# LowVBoard_01.net
KiCad netlist of a schematic drawn in EAGLE
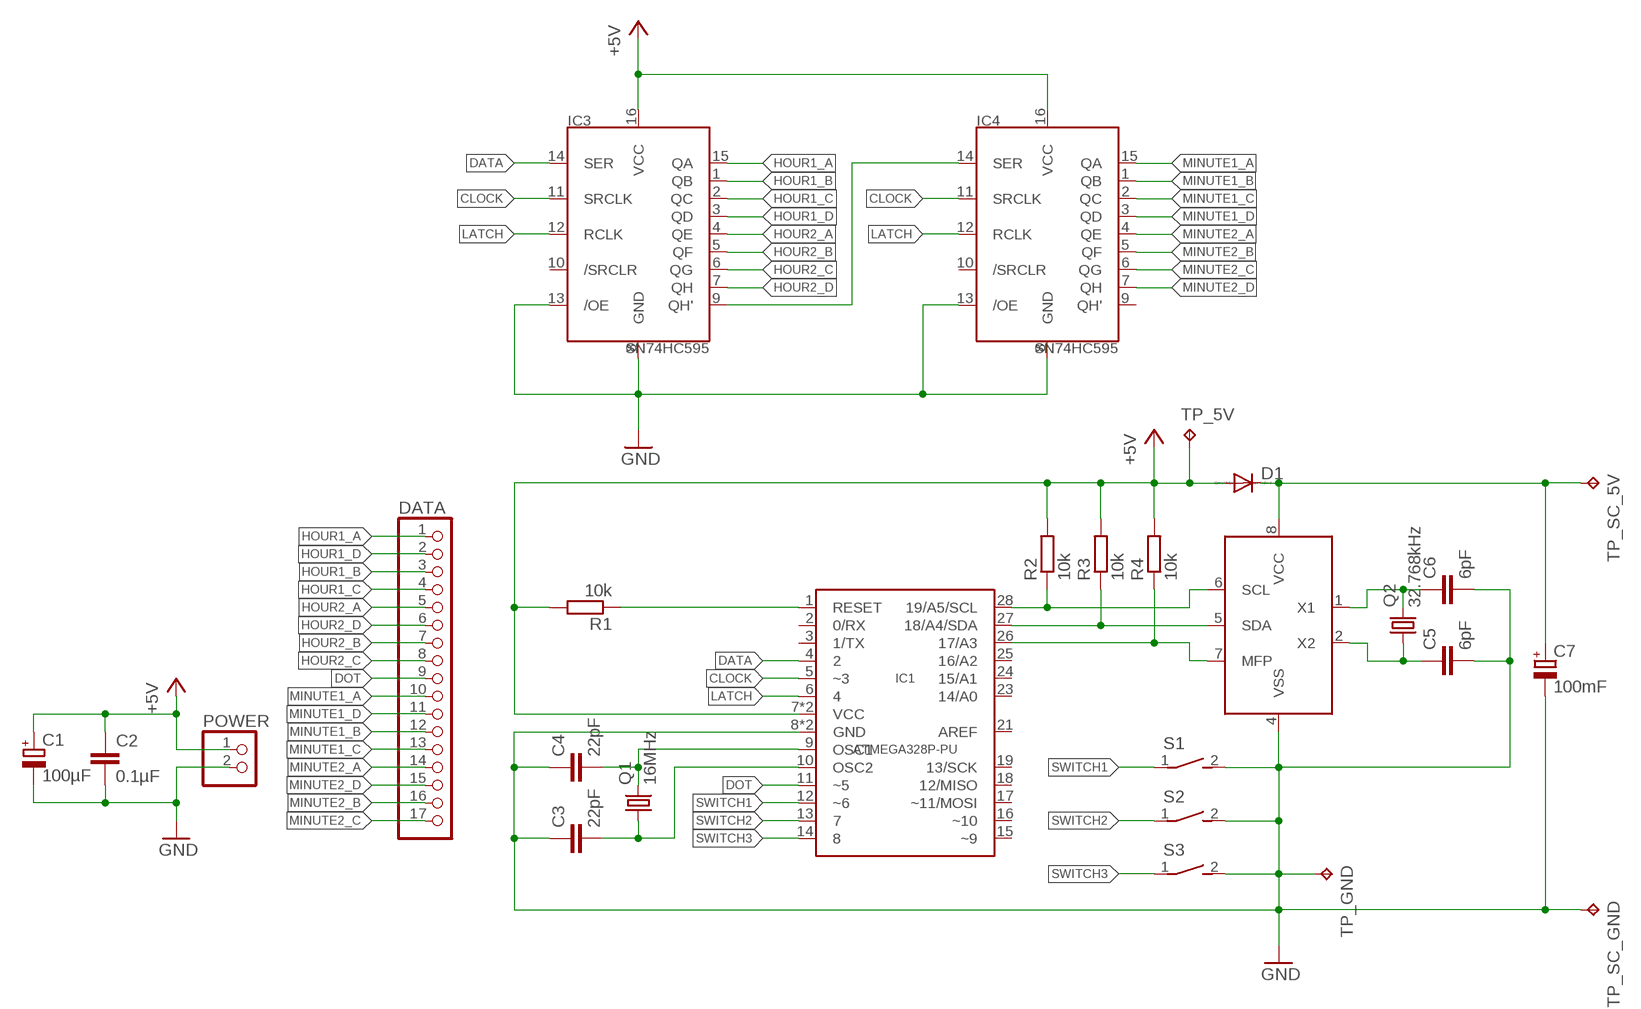
[diagram p0: schematic, sheet 1]

(export (version "E")
  (design (tool "Eeschema 10.0.6"))
  (components
    (comp (ref "C1")
      (value "100µF")
      (footprint "eagle-import:E2-5")
      (libsource (lib "eagle-import") (part "CPOL-EUE2-5"))
    )
    (comp (ref "C2")
      (value "0.1µF")
      (footprint "eagle-import:C025-024X044")
      (libsource (lib "eagle-import") (part "C-EU025-024X044"))
    )
    (comp (ref "C3")
      (value "22pF")
      (footprint "eagle-import:C025-024X044")
      (libsource (lib "eagle-import") (part "C-EU025-024X044"))
    )
    (comp (ref "C4")
      (value "22pF")
      (footprint "eagle-import:C025-024X044")
      (libsource (lib "eagle-import") (part "C-EU025-024X044"))
    )
    (comp (ref "C5")
      (value "6pF")
      (footprint "eagle-import:C025-024X044")
      (libsource (lib "eagle-import") (part "C-EU025-024X044"))
    )
    (comp (ref "C6")
      (value "6pF")
      (footprint "eagle-import:C025-024X044")
      (libsource (lib "eagle-import") (part "C-EU025-024X044"))
    )
    (comp (ref "C7")
      (value "100mF")
      (footprint "eagle-import:SUPERCAP-11.5")
      (libsource (lib "eagle-import") (part "FTW0H104ZF"))
    )
    (comp (ref "D1")
      (value "DIODE-DO201-15")
      (footprint "eagle-import:DO201-15")
      (libsource (lib "eagle-import") (part "DIODE-DO201-15"))
    )
    (comp (ref "DATA")
      (value "PINHD-1X17")
      (footprint "eagle-import:1X17")
      (libsource (lib "eagle-import") (part "PINHD-1X17"))
    )
    (comp (ref "IC1")
      (value "ATMEGA328P-PU")
      (footprint "eagle-import:DIP28")
      (libsource (lib "eagle-import") (part "ATMEGA328P-PU"))
    )
    (comp (ref "IC2")
      (value "MCP7940M")
      (footprint "eagle-import:DIL8")
      (libsource (lib "eagle-import") (part "MCP7940M-I/P"))
    )
    (comp (ref "IC3")
      (value "SN74HC595")
      (footprint "eagle-import:DIL16")
      (libsource (lib "eagle-import") (part "SN74HC595"))
    )
    (comp (ref "IC4")
      (value "SN74HC595")
      (footprint "eagle-import:DIL16")
      (libsource (lib "eagle-import") (part "SN74HC595"))
    )
    (comp (ref "POWER")
      (value "PINHD-1X2")
      (footprint "eagle-import:1X02")
      (libsource (lib "eagle-import") (part "PINHD-1X2"))
    )
    (comp (ref "Q1")
      (value "16MHz")
      (footprint "eagle-import:HC49_S")
      (libsource (lib "eagle-import") (part "CRYSTALHC49S"))
    )
    (comp (ref "Q2")
      (value "32.768kHz")
      (footprint "eagle-import:CFS-206")
      (libsource (lib "eagle-import") (part "CFS-206"))
    )
    (comp (ref "R1")
      (value "10k")
      (footprint "eagle-import:0207_7")
      (libsource (lib "eagle-import") (part "R-EU_0207/7"))
    )
    (comp (ref "R2")
      (value "10k")
      (footprint "eagle-import:0207_7")
      (libsource (lib "eagle-import") (part "R-EU_0207/7"))
    )
    (comp (ref "R3")
      (value "10k")
      (footprint "eagle-import:0207_7")
      (libsource (lib "eagle-import") (part "R-EU_0207/7"))
    )
    (comp (ref "R4")
      (value "10k")
      (footprint "eagle-import:0207_7")
      (libsource (lib "eagle-import") (part "R-EU_0207/7"))
    )
    (comp (ref "S1")
      (value "GPTS203211B")
      (footprint "eagle-import:GPTS203211B")
      (libsource (lib "eagle-import") (part "GPTS203211B"))
    )
    (comp (ref "S2")
      (value "GPTS203211B")
      (footprint "eagle-import:GPTS203211B")
      (libsource (lib "eagle-import") (part "GPTS203211B"))
    )
    (comp (ref "S3")
      (value "GPTS203211B")
      (footprint "eagle-import:GPTS203211B")
      (libsource (lib "eagle-import") (part "GPTS203211B"))
    )
    (comp (ref "TP_5V")
      (value "TPPAD1-13")
      (footprint "eagle-import:P1-13")
      (libsource (lib "eagle-import") (part "TPPAD1-13"))
    )
    (comp (ref "TP_GND")
      (value "TPPAD1-13")
      (footprint "eagle-import:P1-13")
      (libsource (lib "eagle-import") (part "TPPAD1-13"))
    )
    (comp (ref "TP_SC_5V")
      (value "TPPAD1-13")
      (footprint "eagle-import:P1-13")
      (libsource (lib "eagle-import") (part "TPPAD1-13"))
    )
    (comp (ref "TP_SC_GND")
      (value "TPPAD1-13")
      (footprint "eagle-import:P1-13")
      (libsource (lib "eagle-import") (part "TPPAD1-13"))
    )
  )
  (nets
    (net (code "1") (name "+5V") (class "Default")
      (node (ref "C1") (pin "+") (pinfunction "+_+") (pintype "passive"))
      (node (ref "C2") (pin "1") (pinfunction "1_1") (pintype "passive"))
      (node (ref "D1") (pin "A") (pinfunction "A_A") (pintype "passive"))
      (node (ref "IC1") (pin "20") (pinfunction "VCC_20") (pintype "bidirectional"))
      (node (ref "IC1") (pin "7") (pinfunction "VCC_7") (pintype "bidirectional"))
      (node (ref "IC3") (pin "16") (pinfunction "VCC_16") (pintype "bidirectional"))
      (node (ref "IC4") (pin "16") (pinfunction "VCC_16") (pintype "bidirectional"))
      (node (ref "POWER") (pin "1") (pinfunction "1_1") (pintype "passive"))
      (node (ref "R1") (pin "2") (pinfunction "2_2") (pintype "passive"))
      (node (ref "R2") (pin "2") (pinfunction "2_2") (pintype "passive"))
      (node (ref "R3") (pin "2") (pinfunction "2_2") (pintype "passive"))
      (node (ref "R4") (pin "2") (pinfunction "2_2") (pintype "passive"))
      (node (ref "TP_5V") (pin "TP") (pinfunction "TP_TP") (pintype "input"))
    )
    (net (code "2") (name "CLOCK") (class "Default")
      (node (ref "IC1") (pin "5") (pinfunction "~{3}_5") (pintype "bidirectional"))
      (node (ref "IC3") (pin "11") (pinfunction "SRCLK_11") (pintype "bidirectional"))
      (node (ref "IC4") (pin "11") (pinfunction "SRCLK_11") (pintype "bidirectional"))
    )
    (net (code "3") (name "DATA") (class "Default")
      (node (ref "IC1") (pin "4") (pinfunction "2_4") (pintype "bidirectional"))
      (node (ref "IC3") (pin "14") (pinfunction "SER_14") (pintype "bidirectional"))
    )
    (net (code "4") (name "DOT") (class "Default")
      (node (ref "DATA") (pin "9") (pinfunction "9_9") (pintype "passive"))
      (node (ref "IC1") (pin "11") (pinfunction "~{5}_11") (pintype "bidirectional"))
    )
    (net (code "5") (name "GND") (class "Default")
      (node (ref "C1") (pin "-") (pinfunction "-_-") (pintype "passive"))
      (node (ref "C2") (pin "2") (pinfunction "2_2") (pintype "passive"))
      (node (ref "C3") (pin "1") (pinfunction "1_1") (pintype "passive"))
      (node (ref "C4") (pin "1") (pinfunction "1_1") (pintype "passive"))
      (node (ref "C5") (pin "2") (pinfunction "2_2") (pintype "passive"))
      (node (ref "C6") (pin "2") (pinfunction "2_2") (pintype "passive"))
      (node (ref "C7") (pin "-") (pinfunction "-_-") (pintype "passive"))
      (node (ref "IC1") (pin "22") (pinfunction "GND_22") (pintype "bidirectional"))
      (node (ref "IC1") (pin "8") (pinfunction "GND_8") (pintype "bidirectional"))
      (node (ref "IC2") (pin "4") (pinfunction "VSS_4") (pintype "bidirectional"))
      (node (ref "IC3") (pin "13") (pinfunction "/OE_13") (pintype "bidirectional"))
      (node (ref "IC3") (pin "8") (pinfunction "GND_8") (pintype "bidirectional"))
      (node (ref "IC4") (pin "13") (pinfunction "/OE_13") (pintype "bidirectional"))
      (node (ref "IC4") (pin "8") (pinfunction "GND_8") (pintype "bidirectional"))
      (node (ref "POWER") (pin "2") (pinfunction "2_2") (pintype "passive"))
      (node (ref "S1") (pin "2") (pinfunction "S_2") (pintype "passive"))
      (node (ref "S2") (pin "2") (pinfunction "S_2") (pintype "passive"))
      (node (ref "S3") (pin "2") (pinfunction "S_2") (pintype "passive"))
      (node (ref "TP_GND") (pin "TP") (pinfunction "TP_TP") (pintype "input"))
      (node (ref "TP_SC_GND") (pin "TP") (pinfunction "TP_TP") (pintype "input"))
    )
    (net (code "6") (name "HOUR1_A") (class "Default")
      (node (ref "DATA") (pin "1") (pinfunction "1_1") (pintype "passive"))
      (node (ref "IC3") (pin "15") (pinfunction "QA_15") (pintype "bidirectional"))
    )
    (net (code "7") (name "HOUR1_B") (class "Default")
      (node (ref "DATA") (pin "3") (pinfunction "3_3") (pintype "passive"))
      (node (ref "IC3") (pin "1") (pinfunction "QB_1") (pintype "bidirectional"))
    )
    (net (code "8") (name "HOUR1_C") (class "Default")
      (node (ref "DATA") (pin "4") (pinfunction "4_4") (pintype "passive"))
      (node (ref "IC3") (pin "2") (pinfunction "QC_2") (pintype "bidirectional"))
    )
    (net (code "9") (name "HOUR1_D") (class "Default")
      (node (ref "DATA") (pin "2") (pinfunction "2_2") (pintype "passive"))
      (node (ref "IC3") (pin "3") (pinfunction "QD_3") (pintype "bidirectional"))
    )
    (net (code "10") (name "HOUR2_A") (class "Default")
      (node (ref "DATA") (pin "5") (pinfunction "5_5") (pintype "passive"))
      (node (ref "IC3") (pin "4") (pinfunction "QE_4") (pintype "bidirectional"))
    )
    (net (code "11") (name "HOUR2_B") (class "Default")
      (node (ref "DATA") (pin "7") (pinfunction "7_7") (pintype "passive"))
      (node (ref "IC3") (pin "5") (pinfunction "QF_5") (pintype "bidirectional"))
    )
    (net (code "12") (name "HOUR2_C") (class "Default")
      (node (ref "DATA") (pin "8") (pinfunction "8_8") (pintype "passive"))
      (node (ref "IC3") (pin "6") (pinfunction "QG_6") (pintype "bidirectional"))
    )
    (net (code "13") (name "HOUR2_D") (class "Default")
      (node (ref "DATA") (pin "6") (pinfunction "6_6") (pintype "passive"))
      (node (ref "IC3") (pin "7") (pinfunction "QH_7") (pintype "bidirectional"))
    )
    (net (code "14") (name "LATCH") (class "Default")
      (node (ref "IC1") (pin "6") (pinfunction "4_6") (pintype "bidirectional"))
      (node (ref "IC3") (pin "12") (pinfunction "RCLK_12") (pintype "bidirectional"))
      (node (ref "IC4") (pin "12") (pinfunction "RCLK_12") (pintype "bidirectional"))
    )
    (net (code "15") (name "MINUTE1_A") (class "Default")
      (node (ref "DATA") (pin "10") (pinfunction "10_10") (pintype "passive"))
      (node (ref "IC4") (pin "15") (pinfunction "QA_15") (pintype "bidirectional"))
    )
    (net (code "16") (name "MINUTE1_B") (class "Default")
      (node (ref "DATA") (pin "12") (pinfunction "12_12") (pintype "passive"))
      (node (ref "IC4") (pin "1") (pinfunction "QB_1") (pintype "bidirectional"))
    )
    (net (code "17") (name "MINUTE1_C") (class "Default")
      (node (ref "DATA") (pin "13") (pinfunction "13_13") (pintype "passive"))
      (node (ref "IC4") (pin "2") (pinfunction "QC_2") (pintype "bidirectional"))
    )
    (net (code "18") (name "MINUTE1_D") (class "Default")
      (node (ref "DATA") (pin "11") (pinfunction "11_11") (pintype "passive"))
      (node (ref "IC4") (pin "3") (pinfunction "QD_3") (pintype "bidirectional"))
    )
    (net (code "19") (name "MINUTE2_A") (class "Default")
      (node (ref "DATA") (pin "14") (pinfunction "14_14") (pintype "passive"))
      (node (ref "IC4") (pin "4") (pinfunction "QE_4") (pintype "bidirectional"))
    )
    (net (code "20") (name "MINUTE2_B") (class "Default")
      (node (ref "DATA") (pin "16") (pinfunction "16_16") (pintype "passive"))
      (node (ref "IC4") (pin "5") (pinfunction "QF_5") (pintype "bidirectional"))
    )
    (net (code "21") (name "MINUTE2_C") (class "Default")
      (node (ref "DATA") (pin "17") (pinfunction "17_17") (pintype "passive"))
      (node (ref "IC4") (pin "6") (pinfunction "QG_6") (pintype "bidirectional"))
    )
    (net (code "22") (name "MINUTE2_D") (class "Default")
      (node (ref "DATA") (pin "15") (pinfunction "15_15") (pintype "passive"))
      (node (ref "IC4") (pin "7") (pinfunction "QH_7") (pintype "bidirectional"))
    )
    (net (code "23") (name "Net-(IC1-17{slash}A3)") (class "Default")
      (node (ref "IC1") (pin "26") (pinfunction "17/A3_26") (pintype "bidirectional"))
      (node (ref "IC2") (pin "7") (pinfunction "MFP_7") (pintype "bidirectional"))
      (node (ref "R4") (pin "1") (pinfunction "1_1") (pintype "passive"))
    )
    (net (code "24") (name "Net-(IC1-18{slash}A4{slash}SDA)") (class "Default")
      (node (ref "IC1") (pin "27") (pinfunction "18/A4/SDA_27") (pintype "bidirectional"))
      (node (ref "IC2") (pin "5") (pinfunction "SDA_5") (pintype "bidirectional"))
      (node (ref "R3") (pin "1") (pinfunction "1_1") (pintype "passive"))
    )
    (net (code "25") (name "Net-(IC1-19{slash}A5{slash}SCL)") (class "Default")
      (node (ref "IC1") (pin "28") (pinfunction "19/A5/SCL_28") (pintype "bidirectional"))
      (node (ref "IC2") (pin "6") (pinfunction "SCL_6") (pintype "bidirectional"))
      (node (ref "R2") (pin "1") (pinfunction "1_1") (pintype "passive"))
    )
    (net (code "26") (name "Net-(IC1-OSC1)") (class "Default")
      (node (ref "C4") (pin "2") (pinfunction "2_2") (pintype "passive"))
      (node (ref "IC1") (pin "9") (pinfunction "OSC1_9") (pintype "bidirectional"))
      (node (ref "Q1") (pin "2") (pinfunction "2_2") (pintype "passive"))
    )
    (net (code "27") (name "Net-(IC1-OSC2)") (class "Default")
      (node (ref "C3") (pin "2") (pinfunction "2_2") (pintype "passive"))
      (node (ref "IC1") (pin "10") (pinfunction "OSC2_10") (pintype "bidirectional"))
      (node (ref "Q1") (pin "1") (pinfunction "1_1") (pintype "passive"))
    )
    (net (code "28") (name "Net-(IC1-RESET)") (class "Default")
      (node (ref "IC1") (pin "1") (pinfunction "RESET_1") (pintype "bidirectional"))
      (node (ref "R1") (pin "1") (pinfunction "1_1") (pintype "passive"))
    )
    (net (code "29") (name "Net-(IC2-VCC)") (class "Default")
      (node (ref "C7") (pin "+") (pinfunction "+_+") (pintype "passive"))
      (node (ref "D1") (pin "C") (pinfunction "C_C") (pintype "passive"))
      (node (ref "IC2") (pin "8") (pinfunction "VCC_8") (pintype "bidirectional"))
      (node (ref "TP_SC_5V") (pin "TP") (pinfunction "TP_TP") (pintype "input"))
    )
    (net (code "30") (name "Net-(IC2-X1)") (class "Default")
      (node (ref "C6") (pin "1") (pinfunction "1_1") (pintype "passive"))
      (node (ref "IC2") (pin "1") (pinfunction "X1_1") (pintype "bidirectional"))
      (node (ref "Q2") (pin "P$2") (pinfunction "2_P$2") (pintype "passive"))
    )
    (net (code "31") (name "Net-(IC2-X2)") (class "Default")
      (node (ref "C5") (pin "1") (pinfunction "1_1") (pintype "passive"))
      (node (ref "IC2") (pin "2") (pinfunction "X2_2") (pintype "bidirectional"))
      (node (ref "Q2") (pin "P$1") (pinfunction "1_P$1") (pintype "passive"))
    )
    (net (code "32") (name "Net-(IC3-QH')") (class "Default")
      (node (ref "IC3") (pin "9") (pinfunction "QH'_9") (pintype "bidirectional"))
      (node (ref "IC4") (pin "14") (pinfunction "SER_14") (pintype "bidirectional"))
    )
    (net (code "33") (name "SWITCH1") (class "Default")
      (node (ref "IC1") (pin "12") (pinfunction "~{6}_12") (pintype "bidirectional"))
      (node (ref "S1") (pin "1") (pinfunction "P_1") (pintype "passive"))
    )
    (net (code "34") (name "SWITCH2") (class "Default")
      (node (ref "IC1") (pin "13") (pinfunction "7_13") (pintype "bidirectional"))
      (node (ref "S2") (pin "1") (pinfunction "P_1") (pintype "passive"))
    )
    (net (code "35") (name "SWITCH3") (class "Default")
      (node (ref "IC1") (pin "14") (pinfunction "8_14") (pintype "bidirectional"))
      (node (ref "S3") (pin "1") (pinfunction "P_1") (pintype "passive"))
    )
    (net (code "36") (name "unconnected-(IC1-0{slash}RX-Pad2)") (class "Default")
      (node (ref "IC1") (pin "2") (pinfunction "0/RX_2") (pintype "bidirectional"))
    )
    (net (code "37") (name "unconnected-(IC1-1{slash}TX-Pad3)") (class "Default")
      (node (ref "IC1") (pin "3") (pinfunction "1/TX_3") (pintype "bidirectional"))
    )
    (net (code "38") (name "unconnected-(IC1-12{slash}MISO-Pad18)") (class "Default")
      (node (ref "IC1") (pin "18") (pinfunction "12/MISO_18") (pintype "bidirectional"))
    )
    (net (code "39") (name "unconnected-(IC1-13{slash}SCK-Pad19)") (class "Default")
      (node (ref "IC1") (pin "19") (pinfunction "13/SCK_19") (pintype "bidirectional"))
    )
    (net (code "40") (name "unconnected-(IC1-14{slash}A0-Pad23)") (class "Default")
      (node (ref "IC1") (pin "23") (pinfunction "14/A0_23") (pintype "bidirectional"))
    )
    (net (code "41") (name "unconnected-(IC1-15{slash}A1-Pad24)") (class "Default")
      (node (ref "IC1") (pin "24") (pinfunction "15/A1_24") (pintype "bidirectional"))
    )
    (net (code "42") (name "unconnected-(IC1-16{slash}A2-Pad25)") (class "Default")
      (node (ref "IC1") (pin "25") (pinfunction "16/A2_25") (pintype "bidirectional"))
    )
    (net (code "43") (name "unconnected-(IC1-AREF-Pad21)") (class "Default")
      (node (ref "IC1") (pin "21") (pinfunction "AREF_21") (pintype "bidirectional"))
    )
    (net (code "44") (name "unconnected-(IC1-~{9}-Pad15)") (class "Default")
      (node (ref "IC1") (pin "15") (pinfunction "~{9}_15") (pintype "bidirectional"))
    )
    (net (code "45") (name "unconnected-(IC1-~{10}-Pad16)") (class "Default")
      (node (ref "IC1") (pin "16") (pinfunction "~{10}_16") (pintype "bidirectional"))
    )
    (net (code "46") (name "unconnected-(IC1-~{11{slash}MOSI}-Pad17)") (class "Default")
      (node (ref "IC1") (pin "17") (pinfunction "~{11/MOSI}_17") (pintype "bidirectional"))
    )
    (net (code "47") (name "unconnected-(IC3-{slash}SRCLR-Pad10)") (class "Default")
      (node (ref "IC3") (pin "10") (pinfunction "/SRCLR_10") (pintype "bidirectional"))
    )
    (net (code "48") (name "unconnected-(IC4-QH'-Pad9)") (class "Default")
      (node (ref "IC4") (pin "9") (pinfunction "QH'_9") (pintype "bidirectional"))
    )
    (net (code "49") (name "unconnected-(IC4-{slash}SRCLR-Pad10)") (class "Default")
      (node (ref "IC4") (pin "10") (pinfunction "/SRCLR_10") (pintype "bidirectional"))
    )
  )
)
